# NancyHacker.net
KiCad netlist of a schematic drawn in EAGLE
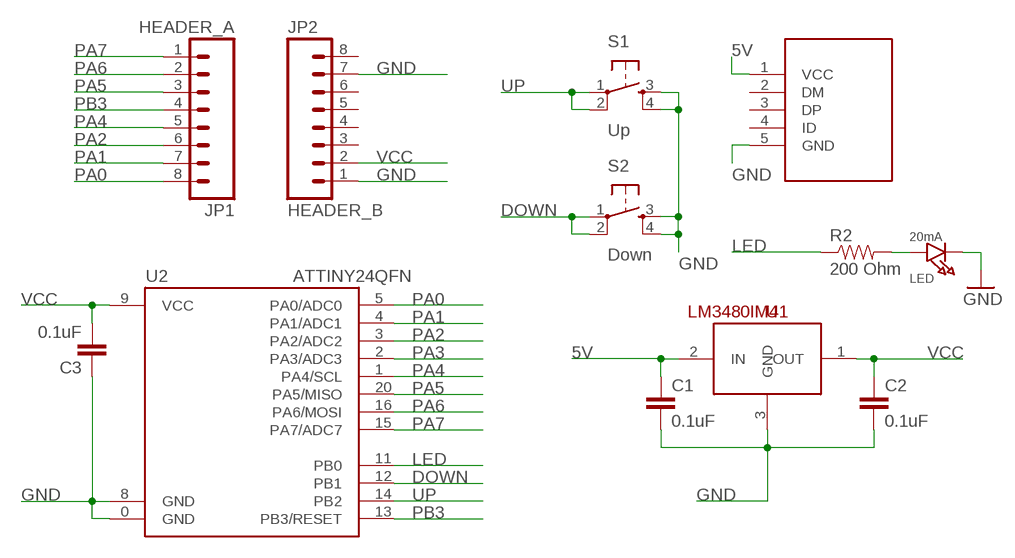
[diagram p0: schematic, sheet 1]

(export (version "E")
  (design (tool "Eeschema 10.0.6"))
  (components
    (comp (ref "C1")
      (value "0.1uF")
      (footprint "eagle-import:0603-CAP")
      (libsource (lib "eagle-import") (part "CAP0603-CAP"))
    )
    (comp (ref "C2")
      (value "0.1uF")
      (footprint "eagle-import:0603-CAP")
      (libsource (lib "eagle-import") (part "CAP0603-CAP"))
    )
    (comp (ref "C3")
      (value "0.1uF")
      (footprint "eagle-import:0603-CAP")
      (libsource (lib "eagle-import") (part "CAP0603-CAP"))
    )
    (comp (ref "JP1")
      (value "HEADER_A")
      (footprint "eagle-import:1X08")
      (libsource (lib "eagle-import") (part "M081X08"))
    )
    (comp (ref "JP2")
      (value "HEADER_B")
      (footprint "eagle-import:1X08")
      (libsource (lib "eagle-import") (part "M081X08"))
    )
    (comp (ref "LED")
      (value "20mA")
      (footprint "eagle-import:CHIPLED_0603_NOOUTLINE")
      (libsource (lib "eagle-import") (part "LED0603_NOOUTLINE"))
    )
    (comp (ref "R2")
      (value "200 Ohm")
      (footprint "eagle-import:0402-RES")
      (libsource (lib "eagle-import") (part "RESISTOR0402-RES"))
    )
    (comp (ref "S1")
      (value "Up")
      (footprint "eagle-import:TACTILE_SWITCH_SMD")
      (libsource (lib "eagle-import") (part "TAC_SWITCHSMD"))
    )
    (comp (ref "S2")
      (value "Down")
      (footprint "eagle-import:TACTILE_SWITCH_SMD")
      (libsource (lib "eagle-import") (part "TAC_SWITCHSMD"))
    )
    (comp (ref "U$1")
      (value "USB-MICROB-SMDRECEPT")
      (footprint "eagle-import:USB-MICROB-RECEPT")
      (libsource (lib "eagle-import") (part "USB-MICROB-SMDRECEPT"))
    )
    (comp (ref "U1")
      (value "LM3480IM4")
      (footprint "eagle-import:SOT23-3")
      (libsource (lib "eagle-import") (part "LM3480IM4"))
    )
    (comp (ref "U2")
      (value "ATTINY24QFN")
      (footprint "eagle-import:QFN20")
      (libsource (lib "eagle-import") (part "ATTINY24QFN"))
    )
  )
  (nets
    (net (code "1") (name "/5V") (class "Default")
      (node (ref "C1") (pin "1") (pinfunction "1_1") (pintype "passive"))
      (node (ref "U$1") (pin "1") (pinfunction "VCC_1") (pintype "bidirectional"))
      (node (ref "U1") (pin "2") (pinfunction "IN_2") (pintype "bidirectional"))
    )
    (net (code "2") (name "/DOWN") (class "Default")
      (node (ref "S2") (pin "1") (pinfunction "1_1") (pintype "passive"))
      (node (ref "S2") (pin "2") (pinfunction "2_2") (pintype "passive"))
      (node (ref "U2") (pin "12") (pinfunction "PB1_12") (pintype "bidirectional"))
    )
    (net (code "3") (name "/LED") (class "Default")
      (node (ref "R2") (pin "1") (pinfunction "1_1") (pintype "passive"))
      (node (ref "U2") (pin "11") (pinfunction "PB0_11") (pintype "bidirectional"))
    )
    (net (code "4") (name "/PA0") (class "Default")
      (node (ref "JP1") (pin "8") (pinfunction "8_8") (pintype "passive"))
      (node (ref "U2") (pin "5") (pinfunction "PA0/ADC0_5") (pintype "bidirectional"))
    )
    (net (code "5") (name "/PA1") (class "Default")
      (node (ref "JP1") (pin "7") (pinfunction "7_7") (pintype "passive"))
      (node (ref "U2") (pin "4") (pinfunction "PA1/ADC1_4") (pintype "bidirectional"))
    )
    (net (code "6") (name "/PA2") (class "Default")
      (node (ref "JP1") (pin "6") (pinfunction "6_6") (pintype "passive"))
      (node (ref "U2") (pin "3") (pinfunction "PA2/ADC2_3") (pintype "bidirectional"))
    )
    (net (code "7") (name "/PA3") (class "Default")
      (node (ref "U2") (pin "2") (pinfunction "PA3/ADC3_2") (pintype "bidirectional"))
    )
    (net (code "8") (name "/PA4") (class "Default")
      (node (ref "JP1") (pin "5") (pinfunction "5_5") (pintype "passive"))
      (node (ref "U2") (pin "1") (pinfunction "PA4/SCL_1") (pintype "bidirectional"))
    )
    (net (code "9") (name "/PA5") (class "Default")
      (node (ref "JP1") (pin "3") (pinfunction "3_3") (pintype "passive"))
      (node (ref "U2") (pin "20") (pinfunction "PA5/MISO_20") (pintype "bidirectional"))
    )
    (net (code "10") (name "/PA6") (class "Default")
      (node (ref "JP1") (pin "2") (pinfunction "2_2") (pintype "passive"))
      (node (ref "U2") (pin "16") (pinfunction "PA6/MOSI_16") (pintype "bidirectional"))
    )
    (net (code "11") (name "/PA7") (class "Default")
      (node (ref "JP1") (pin "1") (pinfunction "1_1") (pintype "passive"))
      (node (ref "U2") (pin "15") (pinfunction "PA7/ADC7_15") (pintype "bidirectional"))
    )
    (net (code "12") (name "/PB3") (class "Default")
      (node (ref "JP1") (pin "4") (pinfunction "4_4") (pintype "passive"))
      (node (ref "U2") (pin "13") (pinfunction "PB3/RESET_13") (pintype "bidirectional"))
    )
    (net (code "13") (name "/UP") (class "Default")
      (node (ref "S1") (pin "1") (pinfunction "1_1") (pintype "passive"))
      (node (ref "S1") (pin "2") (pinfunction "2_2") (pintype "passive"))
      (node (ref "U2") (pin "14") (pinfunction "PB2_14") (pintype "bidirectional"))
    )
    (net (code "14") (name "/VCC") (class "Default")
      (node (ref "C2") (pin "1") (pinfunction "1_1") (pintype "passive"))
      (node (ref "C3") (pin "2") (pinfunction "2_2") (pintype "passive"))
      (node (ref "JP2") (pin "2") (pinfunction "2_2") (pintype "passive"))
      (node (ref "U1") (pin "1") (pinfunction "OUT_1") (pintype "bidirectional"))
      (node (ref "U2") (pin "9") (pinfunction "VCC_9") (pintype "bidirectional"))
    )
    (net (code "15") (name "GND") (class "Default")
      (node (ref "C1") (pin "2") (pinfunction "2_2") (pintype "passive"))
      (node (ref "C2") (pin "2") (pinfunction "2_2") (pintype "passive"))
      (node (ref "C3") (pin "1") (pinfunction "1_1") (pintype "passive"))
      (node (ref "JP2") (pin "1") (pinfunction "1_1") (pintype "passive"))
      (node (ref "JP2") (pin "7") (pinfunction "7_7") (pintype "passive"))
      (node (ref "LED") (pin "C") (pinfunction "C_C") (pintype "passive"))
      (node (ref "S1") (pin "3") (pinfunction "3_3") (pintype "passive"))
      (node (ref "S1") (pin "4") (pinfunction "4_4") (pintype "passive"))
      (node (ref "S2") (pin "3") (pinfunction "3_3") (pintype "passive"))
      (node (ref "S2") (pin "4") (pinfunction "4_4") (pintype "passive"))
      (node (ref "U$1") (pin "5") (pinfunction "GND_5") (pintype "bidirectional"))
      (node (ref "U1") (pin "3") (pinfunction "GND_3") (pintype "bidirectional"))
      (node (ref "U2") (pin "0") (pinfunction "GND_0") (pintype "bidirectional"))
      (node (ref "U2") (pin "8") (pinfunction "GND_8") (pintype "bidirectional"))
    )
    (net (code "16") (name "Net-(LED-PadA)") (class "Default")
      (node (ref "LED") (pin "A") (pinfunction "A_A") (pintype "passive"))
      (node (ref "R2") (pin "2") (pinfunction "2_2") (pintype "passive"))
    )
    (net (code "17") (name "unconnected-(JP2-Pad3)") (class "Default")
      (node (ref "JP2") (pin "3") (pinfunction "3_3") (pintype "passive"))
    )
    (net (code "18") (name "unconnected-(JP2-Pad4)") (class "Default")
      (node (ref "JP2") (pin "4") (pinfunction "4_4") (pintype "passive"))
    )
    (net (code "19") (name "unconnected-(JP2-Pad5)") (class "Default")
      (node (ref "JP2") (pin "5") (pinfunction "5_5") (pintype "passive"))
    )
    (net (code "20") (name "unconnected-(JP2-Pad6)") (class "Default")
      (node (ref "JP2") (pin "6") (pinfunction "6_6") (pintype "passive"))
    )
    (net (code "21") (name "unconnected-(JP2-Pad8)") (class "Default")
      (node (ref "JP2") (pin "8") (pinfunction "8_8") (pintype "passive"))
    )
    (net (code "22") (name "unconnected-(U$1-DM-Pad2)") (class "Default")
      (node (ref "U$1") (pin "2") (pinfunction "DM_2") (pintype "bidirectional"))
    )
    (net (code "23") (name "unconnected-(U$1-DP-Pad3)") (class "Default")
      (node (ref "U$1") (pin "3") (pinfunction "DP_3") (pintype "bidirectional"))
    )
    (net (code "24") (name "unconnected-(U$1-ID-Pad4)") (class "Default")
      (node (ref "U$1") (pin "4") (pinfunction "ID_4") (pintype "bidirectional"))
    )
  )
)
